# Connector_-_Carrier.net
KiCad netlist of a schematic drawn in Altium Designer
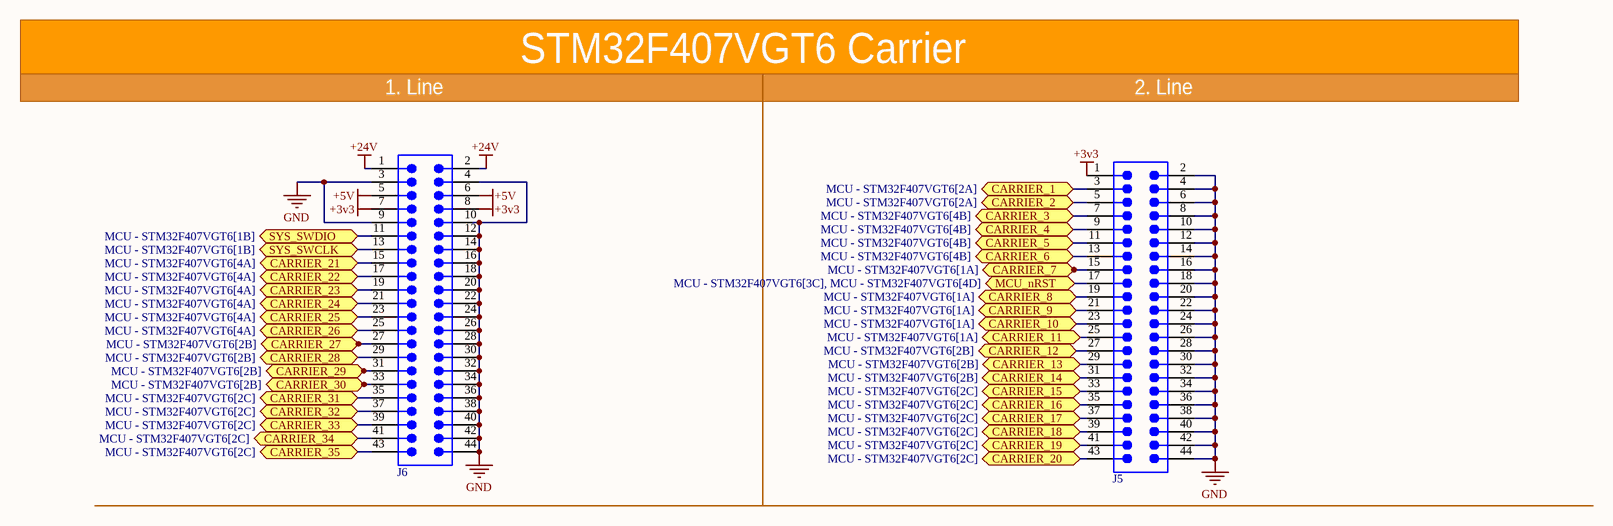
[diagram p0: Connector - Carrier.SchDoc]

(export (version "E")
  (design (tool "Eeschema 10.0.6"))
  (components
    (comp (ref "J5")
      (value "62004421121")
      (footprint "62004421121")
      (description "WR-PHD Pin Header, THT, Vertical, pitch 2mm, 2 Row, 44P")
      (fields (field (name "MANUFACTURER") "Wurth Elektronik"))
      (libsource (lib "MainLibrary") (part "62004421121"))
    )
    (comp (ref "J6")
      (value "62004421121")
      (footprint "62004421121")
      (description "WR-PHD Pin Header, THT, Vertical, pitch 2mm, 2 Row, 44P")
      (fields (field (name "MANUFACTURER") "Wurth Elektronik"))
      (libsource (lib "MainLibrary") (part "62004421121"))
    )
  )
  (nets
    (net (code "1") (name "+3v3") (class "Default")
      (node (ref "J5") (pin "1") (pinfunction "1_1") (pintype "passive"))
      (node (ref "J6") (pin "7") (pinfunction "7_7") (pintype "passive"))
      (node (ref "J6") (pin "8") (pinfunction "8_8") (pintype "passive"))
    )
    (net (code "2") (name "+5V") (class "Default")
      (node (ref "J6") (pin "5") (pinfunction "5_5") (pintype "passive"))
      (node (ref "J6") (pin "6") (pinfunction "6_6") (pintype "passive"))
    )
    (net (code "3") (name "+24V") (class "Default")
      (node (ref "J6") (pin "1") (pinfunction "1_1") (pintype "passive"))
      (node (ref "J6") (pin "2") (pinfunction "2_2") (pintype "passive"))
    )
    (net (code "4") (name "/CARRIER_1") (class "Default")
      (node (ref "J5") (pin "3") (pinfunction "3_3") (pintype "passive"))
    )
    (net (code "5") (name "/CARRIER_2") (class "Default")
      (node (ref "J5") (pin "5") (pinfunction "5_5") (pintype "passive"))
    )
    (net (code "6") (name "/CARRIER_3") (class "Default")
      (node (ref "J5") (pin "7") (pinfunction "7_7") (pintype "passive"))
    )
    (net (code "7") (name "/CARRIER_4") (class "Default")
      (node (ref "J5") (pin "9") (pinfunction "9_9") (pintype "passive"))
    )
    (net (code "8") (name "/CARRIER_5") (class "Default")
      (node (ref "J5") (pin "11") (pinfunction "11_11") (pintype "passive"))
    )
    (net (code "9") (name "/CARRIER_6") (class "Default")
      (node (ref "J5") (pin "13") (pinfunction "13_13") (pintype "passive"))
    )
    (net (code "10") (name "/CARRIER_7") (class "Default")
      (node (ref "J5") (pin "15") (pinfunction "15_15") (pintype "passive"))
    )
    (net (code "11") (name "/CARRIER_8") (class "Default")
      (node (ref "J5") (pin "19") (pinfunction "19_19") (pintype "passive"))
    )
    (net (code "12") (name "/CARRIER_9") (class "Default")
      (node (ref "J5") (pin "21") (pinfunction "21_21") (pintype "passive"))
    )
    (net (code "13") (name "/CARRIER_10") (class "Default")
      (node (ref "J5") (pin "23") (pinfunction "23_23") (pintype "passive"))
    )
    (net (code "14") (name "/CARRIER_11") (class "Default")
      (node (ref "J5") (pin "25") (pinfunction "25_25") (pintype "passive"))
    )
    (net (code "15") (name "/CARRIER_12") (class "Default")
      (node (ref "J5") (pin "27") (pinfunction "27_27") (pintype "passive"))
    )
    (net (code "16") (name "/CARRIER_13") (class "Default")
      (node (ref "J5") (pin "29") (pinfunction "29_29") (pintype "passive"))
    )
    (net (code "17") (name "/CARRIER_14") (class "Default")
      (node (ref "J5") (pin "31") (pinfunction "31_31") (pintype "passive"))
    )
    (net (code "18") (name "/CARRIER_15") (class "Default")
      (node (ref "J5") (pin "33") (pinfunction "33_33") (pintype "passive"))
    )
    (net (code "19") (name "/CARRIER_16") (class "Default")
      (node (ref "J5") (pin "35") (pinfunction "35_35") (pintype "passive"))
    )
    (net (code "20") (name "/CARRIER_17") (class "Default")
      (node (ref "J5") (pin "37") (pinfunction "37_37") (pintype "passive"))
    )
    (net (code "21") (name "/CARRIER_18") (class "Default")
      (node (ref "J5") (pin "39") (pinfunction "39_39") (pintype "passive"))
    )
    (net (code "22") (name "/CARRIER_19") (class "Default")
      (node (ref "J5") (pin "41") (pinfunction "41_41") (pintype "passive"))
    )
    (net (code "23") (name "/CARRIER_20") (class "Default")
      (node (ref "J5") (pin "43") (pinfunction "43_43") (pintype "passive"))
    )
    (net (code "24") (name "/CARRIER_21") (class "Default")
      (node (ref "J6") (pin "15") (pinfunction "15_15") (pintype "passive"))
    )
    (net (code "25") (name "/CARRIER_22") (class "Default")
      (node (ref "J6") (pin "17") (pinfunction "17_17") (pintype "passive"))
    )
    (net (code "26") (name "/CARRIER_23") (class "Default")
      (node (ref "J6") (pin "19") (pinfunction "19_19") (pintype "passive"))
    )
    (net (code "27") (name "/CARRIER_24") (class "Default")
      (node (ref "J6") (pin "21") (pinfunction "21_21") (pintype "passive"))
    )
    (net (code "28") (name "/CARRIER_25") (class "Default")
      (node (ref "J6") (pin "23") (pinfunction "23_23") (pintype "passive"))
    )
    (net (code "29") (name "/CARRIER_26") (class "Default")
      (node (ref "J6") (pin "25") (pinfunction "25_25") (pintype "passive"))
    )
    (net (code "30") (name "/CARRIER_27") (class "Default")
      (node (ref "J6") (pin "27") (pinfunction "27_27") (pintype "passive"))
    )
    (net (code "31") (name "/CARRIER_28") (class "Default")
      (node (ref "J6") (pin "29") (pinfunction "29_29") (pintype "passive"))
    )
    (net (code "32") (name "/CARRIER_29") (class "Default")
      (node (ref "J6") (pin "31") (pinfunction "31_31") (pintype "passive"))
    )
    (net (code "33") (name "/CARRIER_30") (class "Default")
      (node (ref "J6") (pin "33") (pinfunction "33_33") (pintype "passive"))
    )
    (net (code "34") (name "/CARRIER_31") (class "Default")
      (node (ref "J6") (pin "35") (pinfunction "35_35") (pintype "passive"))
    )
    (net (code "35") (name "/CARRIER_32") (class "Default")
      (node (ref "J6") (pin "37") (pinfunction "37_37") (pintype "passive"))
    )
    (net (code "36") (name "/CARRIER_33") (class "Default")
      (node (ref "J6") (pin "39") (pinfunction "39_39") (pintype "passive"))
    )
    (net (code "37") (name "/CARRIER_34") (class "Default")
      (node (ref "J6") (pin "41") (pinfunction "41_41") (pintype "passive"))
    )
    (net (code "38") (name "/CARRIER_35") (class "Default")
      (node (ref "J6") (pin "43") (pinfunction "43_43") (pintype "passive"))
    )
    (net (code "39") (name "/MCU_nRST") (class "Default")
      (node (ref "J5") (pin "17") (pinfunction "17_17") (pintype "passive"))
    )
    (net (code "40") (name "/SYS_SWCLK") (class "Default")
      (node (ref "J6") (pin "13") (pinfunction "13_13") (pintype "passive"))
    )
    (net (code "41") (name "/SYS_SWDIO") (class "Default")
      (node (ref "J6") (pin "11") (pinfunction "11_11") (pintype "passive"))
    )
    (net (code "42") (name "GND") (class "Default")
      (node (ref "J5") (pin "10") (pinfunction "10_10") (pintype "passive"))
      (node (ref "J5") (pin "12") (pinfunction "12_12") (pintype "passive"))
      (node (ref "J5") (pin "14") (pinfunction "14_14") (pintype "passive"))
      (node (ref "J5") (pin "16") (pinfunction "16_16") (pintype "passive"))
      (node (ref "J5") (pin "18") (pinfunction "18_18") (pintype "passive"))
      (node (ref "J5") (pin "2") (pinfunction "2_2") (pintype "passive"))
      (node (ref "J5") (pin "20") (pinfunction "20_20") (pintype "passive"))
      (node (ref "J5") (pin "22") (pinfunction "22_22") (pintype "passive"))
      (node (ref "J5") (pin "24") (pinfunction "24_24") (pintype "passive"))
      (node (ref "J5") (pin "26") (pinfunction "26_26") (pintype "passive"))
      (node (ref "J5") (pin "28") (pinfunction "28_28") (pintype "passive"))
      (node (ref "J5") (pin "30") (pinfunction "30_30") (pintype "passive"))
      (node (ref "J5") (pin "32") (pinfunction "32_32") (pintype "passive"))
      (node (ref "J5") (pin "34") (pinfunction "34_34") (pintype "passive"))
      (node (ref "J5") (pin "36") (pinfunction "36_36") (pintype "passive"))
      (node (ref "J5") (pin "38") (pinfunction "38_38") (pintype "passive"))
      (node (ref "J5") (pin "4") (pinfunction "4_4") (pintype "passive"))
      (node (ref "J5") (pin "40") (pinfunction "40_40") (pintype "passive"))
      (node (ref "J5") (pin "42") (pinfunction "42_42") (pintype "passive"))
      (node (ref "J5") (pin "44") (pinfunction "44_44") (pintype "passive"))
      (node (ref "J5") (pin "6") (pinfunction "6_6") (pintype "passive"))
      (node (ref "J5") (pin "8") (pinfunction "8_8") (pintype "passive"))
      (node (ref "J6") (pin "10") (pinfunction "10_10") (pintype "passive"))
      (node (ref "J6") (pin "12") (pinfunction "12_12") (pintype "passive"))
      (node (ref "J6") (pin "14") (pinfunction "14_14") (pintype "passive"))
      (node (ref "J6") (pin "16") (pinfunction "16_16") (pintype "passive"))
      (node (ref "J6") (pin "18") (pinfunction "18_18") (pintype "passive"))
      (node (ref "J6") (pin "20") (pinfunction "20_20") (pintype "passive"))
      (node (ref "J6") (pin "22") (pinfunction "22_22") (pintype "passive"))
      (node (ref "J6") (pin "24") (pinfunction "24_24") (pintype "passive"))
      (node (ref "J6") (pin "26") (pinfunction "26_26") (pintype "passive"))
      (node (ref "J6") (pin "28") (pinfunction "28_28") (pintype "passive"))
      (node (ref "J6") (pin "3") (pinfunction "3_3") (pintype "passive"))
      (node (ref "J6") (pin "30") (pinfunction "30_30") (pintype "passive"))
      (node (ref "J6") (pin "32") (pinfunction "32_32") (pintype "passive"))
      (node (ref "J6") (pin "34") (pinfunction "34_34") (pintype "passive"))
      (node (ref "J6") (pin "36") (pinfunction "36_36") (pintype "passive"))
      (node (ref "J6") (pin "38") (pinfunction "38_38") (pintype "passive"))
      (node (ref "J6") (pin "4") (pinfunction "4_4") (pintype "passive"))
      (node (ref "J6") (pin "40") (pinfunction "40_40") (pintype "passive"))
      (node (ref "J6") (pin "42") (pinfunction "42_42") (pintype "passive"))
      (node (ref "J6") (pin "44") (pinfunction "44_44") (pintype "passive"))
      (node (ref "J6") (pin "9") (pinfunction "9_9") (pintype "passive"))
    )
  )
)
